# EIT_Teensy_Amplifiers.net
KiCad netlist of a schematic drawn in Altium Designer
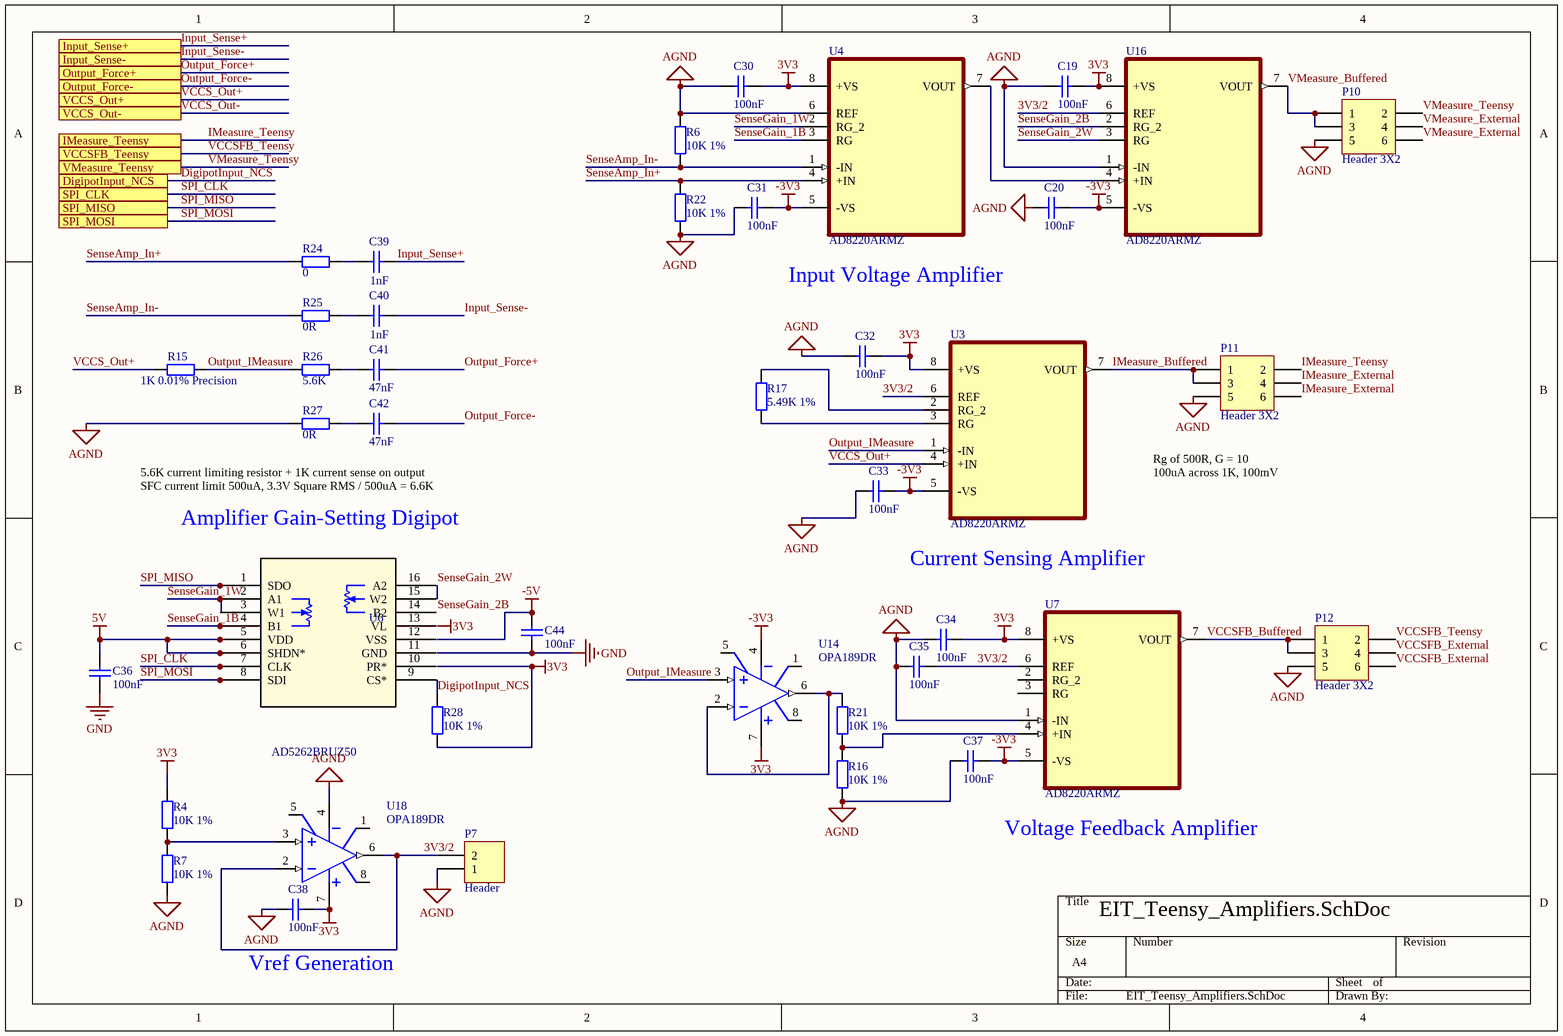
[diagram p0: EIT_Teensy_Amplifiers.SchDoc]

(export (version "E")
  (design (tool "Eeschema 10.0.6"))
  (components
    (comp (ref "C19")
      (value "100nF")
      (footprint "0603 CAP")
      (description "Multi Layer Ceramic Capacitor (MLCC) / Cap Ceramic 0.1uF 50V X7R 10% Pad SMD 0603 125°C T/R")
      (fields
        (field (name "MANUFACTURER") "Samsung")
        (field (name "MANUFACTURER PART NUMBER") "CL10B104KB8NNNC")
      )
      (libsource (lib "EitLib") (part "Cap 0603 100nF 10% 50V"))
    )
    (comp (ref "C20")
      (value "100nF")
      (footprint "0603 CAP")
      (description "Multi Layer Ceramic Capacitor (MLCC) / Cap Ceramic 0.1uF 50V X7R 10% Pad SMD 0603 125°C T/R")
      (fields
        (field (name "MANUFACTURER") "Samsung")
        (field (name "MANUFACTURER PART NUMBER") "CL10B104KB8NNNC")
      )
      (libsource (lib "EitLib") (part "Cap 0603 100nF 10% 50V"))
    )
    (comp (ref "C30")
      (value "100nF")
      (footprint "0603 CAP")
      (description "Multi Layer Ceramic Capacitor (MLCC) / Cap Ceramic 0.1uF 50V X7R 10% Pad SMD 0603 125°C T/R")
      (fields
        (field (name "MANUFACTURER") "Samsung")
        (field (name "MANUFACTURER PART NUMBER") "CL10B104KB8NNNC")
      )
      (libsource (lib "EitLib") (part "Cap 0603 100nF 10% 50V"))
    )
    (comp (ref "C31")
      (value "100nF")
      (footprint "0603 CAP")
      (description "Multi Layer Ceramic Capacitor (MLCC) / Cap Ceramic 0.1uF 50V X7R 10% Pad SMD 0603 125°C T/R")
      (fields
        (field (name "MANUFACTURER") "Samsung")
        (field (name "MANUFACTURER PART NUMBER") "CL10B104KB8NNNC")
      )
      (libsource (lib "EitLib") (part "Cap 0603 100nF 10% 50V"))
    )
    (comp (ref "C32")
      (value "100nF")
      (footprint "0603 CAP")
      (description "Multi Layer Ceramic Capacitor (MLCC) / Cap Ceramic 0.1uF 50V X7R 10% Pad SMD 0603 125°C T/R")
      (fields
        (field (name "MANUFACTURER") "Samsung")
        (field (name "MANUFACTURER PART NUMBER") "CL10B104KB8NNNC")
      )
      (libsource (lib "EitLib") (part "Cap 0603 100nF 10% 50V"))
    )
    (comp (ref "C33")
      (value "100nF")
      (footprint "0603 CAP")
      (description "Multi Layer Ceramic Capacitor (MLCC) / Cap Ceramic 0.1uF 50V X7R 10% Pad SMD 0603 125°C T/R")
      (fields
        (field (name "MANUFACTURER") "Samsung")
        (field (name "MANUFACTURER PART NUMBER") "CL10B104KB8NNNC")
      )
      (libsource (lib "EitLib") (part "Cap 0603 100nF 10% 50V"))
    )
    (comp (ref "C34")
      (value "100nF")
      (footprint "0603 CAP")
      (description "Multi Layer Ceramic Capacitor (MLCC) / Cap Ceramic 0.1uF 50V X7R 10% Pad SMD 0603 125°C T/R")
      (fields
        (field (name "MANUFACTURER") "Samsung")
        (field (name "MANUFACTURER PART NUMBER") "CL10B104KB8NNNC")
      )
      (libsource (lib "EitLib") (part "Cap 0603 100nF 10% 50V"))
    )
    (comp (ref "C35")
      (value "100nF")
      (footprint "0603 CAP")
      (description "Multi Layer Ceramic Capacitor (MLCC) / Cap Ceramic 0.1uF 50V X7R 10% Pad SMD 0603 125°C T/R")
      (fields
        (field (name "MANUFACTURER") "Samsung")
        (field (name "MANUFACTURER PART NUMBER") "CL10B104KB8NNNC")
      )
      (libsource (lib "EitLib") (part "Cap 0603 100nF 10% 50V"))
    )
    (comp (ref "C36")
      (value "100nF")
      (footprint "0603 CAP")
      (description "Multi Layer Ceramic Capacitor (MLCC) / Cap Ceramic 0.1uF 50V X7R 10% Pad SMD 0603 125°C T/R")
      (fields
        (field (name "MANUFACTURER") "Samsung")
        (field (name "MANUFACTURER PART NUMBER") "CL10B104KB8NNNC")
      )
      (libsource (lib "EitLib") (part "Cap 0603 100nF 10% 50V"))
    )
    (comp (ref "C37")
      (value "100nF")
      (footprint "0603 CAP")
      (description "Multi Layer Ceramic Capacitor (MLCC) / Cap Ceramic 0.1uF 50V X7R 10% Pad SMD 0603 125°C T/R")
      (fields
        (field (name "MANUFACTURER") "Samsung")
        (field (name "MANUFACTURER PART NUMBER") "CL10B104KB8NNNC")
      )
      (libsource (lib "EitLib") (part "Cap 0603 100nF 10% 50V"))
    )
    (comp (ref "C38")
      (value "100nF")
      (footprint "0603 CAP")
      (description "Multi Layer Ceramic Capacitor (MLCC) / Cap Ceramic 0.1uF 50V X7R 10% Pad SMD 0603 125°C T/R")
      (fields
        (field (name "MANUFACTURER") "Samsung")
        (field (name "MANUFACTURER PART NUMBER") "CL10B104KB8NNNC")
      )
      (libsource (lib "EitLib") (part "Cap 0603 100nF 10% 50V"))
    )
    (comp (ref "C39")
      (value "1nF")
      (footprint "RAD-0.3")
      (description "Capacitor")
      (fields (field (name "Comment") "Cap") (field (name "PUBLISHER") "Altium Limited"))
      (libsource (lib "Miscellaneous Devices") (part "Cap"))
    )
    (comp (ref "C40")
      (value "1nF")
      (footprint "RAD-0.3")
      (description "Capacitor")
      (fields (field (name "Comment") "Cap") (field (name "PUBLISHER") "Altium Limited"))
      (libsource (lib "Miscellaneous Devices") (part "Cap"))
    )
    (comp (ref "C41")
      (value "47nF")
      (footprint "0603 CAP")
      (description "CAP CER 0.047UF 50V X7R 0603")
      (fields
        (field (name "MANUFACTURER") "Samsung")
        (field (name "MANUFACTURER PART NUMBER") "CL10B473KB8NNNC")
      )
      (libsource (lib "EitLib") (part "Cap 0603 47nF 10% 50V"))
    )
    (comp (ref "C42")
      (value "47nF")
      (footprint "0603 CAP")
      (description "CAP CER 0.047UF 50V X7R 0603")
      (fields
        (field (name "MANUFACTURER") "Samsung")
        (field (name "MANUFACTURER PART NUMBER") "CL10B473KB8NNNC")
      )
      (libsource (lib "EitLib") (part "Cap 0603 47nF 10% 50V"))
    )
    (comp (ref "C44")
      (value "100nF")
      (footprint "0603 CAP")
      (description "Multi Layer Ceramic Capacitor (MLCC) / Cap Ceramic 0.1uF 50V X7R 10% Pad SMD 0603 125°C T/R")
      (fields
        (field (name "MANUFACTURER") "Samsung")
        (field (name "MANUFACTURER PART NUMBER") "CL10B104KB8NNNC")
      )
      (libsource (lib "EitLib") (part "Cap 0603 100nF 10% 50V"))
    )
    (comp (ref "P7")
      (value "Header")
      (footprint "HEADER 2.54MM 2X1 MALE")
      (description "CONN HEADER VERT 2POS 2.54MM")
      (fields
        (field (name "MANUFACTURER") "Sullins")
        (field (name "MANUFACTURER PART NUMBER") "PRPC002SAAN-RC")
      )
      (libsource (lib "EitLib") (part "Header 2x1 2.54mm T/H Male"))
    )
    (comp (ref "P10")
      (value "Header 3X2")
      (footprint "HDR2X3 Male 2.54mm")
      (description "Header, 3-Pin, Dual row")
      (libsource (lib "EitLib") (part "Header 3X2 2.54mm Male"))
    )
    (comp (ref "P11")
      (value "Header 3X2")
      (footprint "HDR2X3 Male 2.54mm")
      (description "Header, 3-Pin, Dual row")
      (libsource (lib "EitLib") (part "Header 3X2 2.54mm Male"))
    )
    (comp (ref "P12")
      (value "Header 3X2")
      (footprint "HDR2X3 Male 2.54mm")
      (description "Header, 3-Pin, Dual row")
      (libsource (lib "EitLib") (part "Header 3X2 2.54mm Male"))
    )
    (comp (ref "R4")
      (value "10K 1%")
      (footprint "0603 RES")
      (description "Res General Purpose Thick Film 0603 10K Ohm 1% 1/10W ±100ppm/°C Molded SMD Paper T/R")
      (fields
        (field (name "MANUFACTURER") "Yageo")
        (field (name "MANUFACTURER PART NUMBER") "RC0603FR-0710KL")
      )
      (libsource (lib "EitLib") (part "Res 0603 10K 1%"))
    )
    (comp (ref "R6")
      (value "10K 1%")
      (footprint "0603 RES")
      (description "Res General Purpose Thick Film 0603 10K Ohm 1% 1/10W ±100ppm/°C Molded SMD Paper T/R")
      (fields
        (field (name "MANUFACTURER") "Yageo")
        (field (name "MANUFACTURER PART NUMBER") "RC0603FR-0710KL")
      )
      (libsource (lib "") (part "Res 0603 10K 1%_1"))
    )
    (comp (ref "R7")
      (value "10K 1%")
      (footprint "0603 RES")
      (description "Res General Purpose Thick Film 0603 10K Ohm 1% 1/10W ±100ppm/°C Molded SMD Paper T/R")
      (fields
        (field (name "MANUFACTURER") "Yageo")
        (field (name "MANUFACTURER PART NUMBER") "RC0603FR-0710KL")
      )
      (libsource (lib "EitLib") (part "Res 0603 10K 1%"))
    )
    (comp (ref "R15")
      (value "1K 0.01% Precision")
      (footprint "0603 RES")
      (description "RES 1K OHM 0.01% 1/10W 0603")
      (fields
        (field (name "MANUFACTURER") "Stackpole Electronics")
        (field (name "MANUFACTURER PART NUMBER") "RNCF0603TKY1K00")
      )
      (libsource (lib "EitLib") (part "Res 0603 1K 0.01%"))
    )
    (comp (ref "R16")
      (value "10K 1%")
      (footprint "0603 RES")
      (description "Res General Purpose Thick Film 0603 10K Ohm 1% 1/10W ±100ppm/°C Molded SMD Paper T/R")
      (fields
        (field (name "MANUFACTURER") "Yageo")
        (field (name "MANUFACTURER PART NUMBER") "RC0603FR-0710KL")
      )
      (libsource (lib "") (part "Res 0603 10K 1%_1"))
    )
    (comp (ref "R17")
      (value "5.49K 1%")
      (footprint "0603 RES")
      (fields
        (field (name "MANUFACTURER") "Yageo")
        (field (name "MANUFACTURER PART NUMBER") "RC0603FR-075K49L")
        (field (name "TOLERANCE") "1%")
      )
      (libsource (lib "EitLib") (part "Res 0603 5.49K 1%"))
    )
    (comp (ref "R21")
      (value "10K 1%")
      (footprint "0603 RES")
      (description "Res General Purpose Thick Film 0603 10K Ohm 1% 1/10W ±100ppm/°C Molded SMD Paper T/R")
      (fields
        (field (name "MANUFACTURER") "Yageo")
        (field (name "MANUFACTURER PART NUMBER") "RC0603FR-0710KL")
      )
      (libsource (lib "") (part "Res 0603 10K 1%_1"))
    )
    (comp (ref "R22")
      (value "10K 1%")
      (footprint "0603 RES")
      (description "Res General Purpose Thick Film 0603 10K Ohm 1% 1/10W ±100ppm/°C Molded SMD Paper T/R")
      (fields
        (field (name "MANUFACTURER") "Yageo")
        (field (name "MANUFACTURER PART NUMBER") "RC0603FR-0710KL")
      )
      (libsource (lib "") (part "Res 0603 10K 1%_1"))
    )
    (comp (ref "R24")
      (value "0")
      (footprint "0603 RES")
      (description "RES SMD 4.7K OHM 1% 1/10W 0603")
      (fields
        (field (name "MANUFACTURER") "Yageo")
        (field (name "MANUFACTURER PART NUMBER") "RC0603FR-074K7L")
      )
      (libsource (lib "EitLib") (part "Res 0603 4.7K 1%"))
    )
    (comp (ref "R25")
      (value "0R")
      (footprint "0603 RES")
      (description "Resistor")
      (libsource (lib "EitLib") (part "Res 0603 template"))
    )
    (comp (ref "R26")
      (value "5.6K")
      (footprint "0603 RES")
      (description "Resistor")
      (libsource (lib "EitLib") (part "Res 0603 template"))
    )
    (comp (ref "R27")
      (value "0R")
      (footprint "0603 RES")
      (description "Resistor")
      (libsource (lib "EitLib") (part "Res 0603 template"))
    )
    (comp (ref "R28")
      (value "10K 1%")
      (footprint "0603 RES")
      (description "Res General Purpose Thick Film 0603 10K Ohm 1% 1/10W ±100ppm/°C Molded SMD Paper T/R")
      (fields
        (field (name "MANUFACTURER") "Yageo")
        (field (name "MANUFACTURER PART NUMBER") "RC0603FR-0710KL")
      )
      (libsource (lib "EitLib") (part "Res 0603 10K 1%"))
    )
    (comp (ref "U3")
      (value "AD8220ARMZ")
      (footprint "SOP65P490X110-8N")
      (description "ANALOG DEVICES   AD8220BRMZ   Instrument Amplifier, 1, 125 V, 2 V/s, 800 kHz,  2.25V to  18V, MSOP")
      (fields
        (field (name "MANUFACTURER") "Analog Devices")
        (field (name "MANUFACTURER PART NUMBER") "AD8220BRMZ")
      )
      (libsource (lib "EitLib") (part "AD8220ARMZ"))
    )
    (comp (ref "U4")
      (value "AD8220ARMZ")
      (footprint "SOP65P490X110-8N")
      (description "ANALOG DEVICES   AD8220BRMZ   Instrument Amplifier, 1, 125 V, 2 V/s, 800 kHz,  2.25V to  18V, MSOP")
      (fields
        (field (name "MANUFACTURER") "Analog Devices")
        (field (name "MANUFACTURER PART NUMBER") "AD8220BRMZ")
      )
      (libsource (lib "EitLib") (part "AD8220ARMZ"))
    )
    (comp (ref "U6")
      (value "AD5262BRUZ50")
      (description "Digital Potentiometer, 2 Func, 50000ohm, 3-wire Serial Control Interface, 256 Positions, PDSO16")
      (fields (field (name "MANUFACTURER") "Analog Devices"))
      (libsource (lib "EitLib") (part "AD5262BRUZ50"))
    )
    (comp (ref "U7")
      (value "AD8220ARMZ")
      (footprint "SOP65P490X110-8N")
      (description "ANALOG DEVICES   AD8220BRMZ   Instrument Amplifier, 1, 125 V, 2 V/s, 800 kHz,  2.25V to  18V, MSOP")
      (fields
        (field (name "MANUFACTURER") "Analog Devices")
        (field (name "MANUFACTURER PART NUMBER") "AD8220BRMZ")
      )
      (libsource (lib "EitLib") (part "AD8220ARMZ"))
    )
    (comp (ref "U14")
      (value "OPA189DR")
      (footprint "8-SOIC")
      (description "36V ZERO DRIFT OP-AMP")
      (fields
        (field (name "MANUFACTURER") "Texas Instruments")
        (field (name "MANUFACTURER PART NUMBER") "OPA189IDR")
      )
      (libsource (lib "EitLib") (part "OpAmp OPA189DR"))
    )
    (comp (ref "U16")
      (value "AD8220ARMZ")
      (footprint "SOP65P490X110-8N")
      (description "ANALOG DEVICES   AD8220BRMZ   Instrument Amplifier, 1, 125 V, 2 V/s, 800 kHz,  2.25V to  18V, MSOP")
      (fields
        (field (name "MANUFACTURER") "Analog Devices")
        (field (name "MANUFACTURER PART NUMBER") "AD8220BRMZ")
      )
      (libsource (lib "EitLib") (part "AD8220ARMZ"))
    )
    (comp (ref "U18")
      (value "OPA189DR")
      (footprint "8-SOIC")
      (description "36V ZERO DRIFT OP-AMP")
      (fields
        (field (name "MANUFACTURER") "Texas Instruments")
        (field (name "MANUFACTURER PART NUMBER") "OPA189IDR")
      )
      (libsource (lib "EitLib") (part "OpAmp OPA189DR"))
    )
  )
  (nets
    (net (code "1") (name "-3V3") (class "Default")
      (node (ref "C20") (pin "2") (pinfunction "2_2") (pintype "passive"))
      (node (ref "C31") (pin "2") (pinfunction "2_2") (pintype "passive"))
      (node (ref "C33") (pin "2") (pinfunction "2_2") (pintype "passive"))
      (node (ref "C37") (pin "2") (pinfunction "2_2") (pintype "passive"))
      (node (ref "U14") (pin "4") (pinfunction "V-_4") (pintype "power_in"))
      (node (ref "U16") (pin "5") (pinfunction "-VS_5") (pintype "power_in"))
      (node (ref "U3") (pin "5") (pinfunction "-VS_5") (pintype "power_in"))
      (node (ref "U4") (pin "5") (pinfunction "-VS_5") (pintype "power_in"))
      (node (ref "U7") (pin "5") (pinfunction "-VS_5") (pintype "power_in"))
    )
    (net (code "2") (name "-5V") (class "Default")
      (node (ref "C44") (pin "2") (pinfunction "2_2") (pintype "passive"))
    )
    (net (code "3") (name "/3V3{slash}2") (class "Default")
      (node (ref "C35") (pin "2") (pinfunction "2_2") (pintype "passive"))
      (node (ref "P7") (pin "2") (pinfunction "2_2") (pintype "passive"))
      (node (ref "U16") (pin "6") (pinfunction "REF_6") (pintype "passive"))
      (node (ref "U18") (pin "2") (pinfunction "IN-_2") (pintype "input"))
      (node (ref "U18") (pin "6") (pinfunction "OUT_6") (pintype "output"))
      (node (ref "U3") (pin "6") (pinfunction "REF_6") (pintype "passive"))
      (node (ref "U7") (pin "6") (pinfunction "REF_6") (pintype "passive"))
    )
    (net (code "4") (name "/DigipotInput_NCS") (class "Default")
      (node (ref "R28") (pin "2") (pinfunction "2_2") (pintype "passive"))
    )
    (net (code "5") (name "/IMeasure_Buffered") (class "Default")
      (node (ref "P11") (pin "1") (pinfunction "1_1") (pintype "passive"))
      (node (ref "P11") (pin "3") (pinfunction "3_3") (pintype "passive"))
      (node (ref "U3") (pin "7") (pinfunction "VOUT_7") (pintype "output"))
    )
    (net (code "6") (name "/IMeasure_External") (class "Default")
      (node (ref "P11") (pin "4") (pinfunction "4_4") (pintype "passive"))
      (node (ref "P11") (pin "6") (pinfunction "6_6") (pintype "passive"))
    )
    (net (code "7") (name "/IMeasure_Teensy") (class "Default")
      (node (ref "P11") (pin "2") (pinfunction "2_2") (pintype "passive"))
    )
    (net (code "8") (name "/Input_Sense+") (class "Default")
      (node (ref "C39") (pin "2") (pinfunction "2_2") (pintype "passive"))
    )
    (net (code "9") (name "/Input_Sense-") (class "Default")
      (node (ref "C40") (pin "2") (pinfunction "2_2") (pintype "passive"))
    )
    (net (code "10") (name "/Output_Force+") (class "Default")
      (node (ref "C41") (pin "2") (pinfunction "2_2") (pintype "passive"))
    )
    (net (code "11") (name "/Output_Force-") (class "Default")
      (node (ref "C42") (pin "2") (pinfunction "2_2") (pintype "passive"))
    )
    (net (code "12") (name "/Output_IMeasure") (class "Default")
      (node (ref "R15") (pin "2") (pinfunction "2_2") (pintype "passive"))
      (node (ref "R26") (pin "1") (pinfunction "1_1") (pintype "passive"))
      (node (ref "U14") (pin "3") (pinfunction "IN+_3") (pintype "input"))
      (node (ref "U3") (pin "1") (pinfunction "-IN_1") (pintype "input"))
    )
    (net (code "13") (name "/SPI_CLK") (class "Default")
      (node (ref "U6") (pin "7") (pinfunction "CLK_7") (pintype "passive"))
    )
    (net (code "14") (name "/SPI_MISO") (class "Default")
      (node (ref "U6") (pin "1") (pinfunction "SDO_1") (pintype "passive"))
    )
    (net (code "15") (name "/SPI_MOSI") (class "Default")
      (node (ref "U6") (pin "8") (pinfunction "SDI_8") (pintype "passive"))
    )
    (net (code "16") (name "/SenseAmp_In+") (class "Default")
      (node (ref "R22") (pin "1") (pinfunction "1_1") (pintype "passive"))
      (node (ref "R24") (pin "1") (pinfunction "1_1") (pintype "passive"))
      (node (ref "U4") (pin "4") (pinfunction "+IN_4") (pintype "input"))
    )
    (net (code "17") (name "/SenseAmp_In-") (class "Default")
      (node (ref "R25") (pin "1") (pinfunction "1_1") (pintype "passive"))
      (node (ref "R6") (pin "2") (pinfunction "2_2") (pintype "passive"))
      (node (ref "U4") (pin "1") (pinfunction "-IN_1") (pintype "input"))
    )
    (net (code "18") (name "/SenseGain_1B") (class "Default")
      (node (ref "U4") (pin "3") (pinfunction "RG_3") (pintype "passive"))
      (node (ref "U6") (pin "4") (pinfunction "B1_4") (pintype "passive"))
    )
    (net (code "19") (name "/SenseGain_1W") (class "Default")
      (node (ref "U4") (pin "2") (pinfunction "RG_2_2") (pintype "passive"))
      (node (ref "U6") (pin "2") (pinfunction "A1_2") (pintype "passive"))
    )
    (net (code "20") (name "/SenseGain_2B") (class "Default")
      (node (ref "U16") (pin "2") (pinfunction "RG_2_2") (pintype "passive"))
    )
    (net (code "21") (name "/SenseGain_2W") (class "Default")
      (node (ref "U16") (pin "3") (pinfunction "RG_3") (pintype "passive"))
    )
    (net (code "22") (name "/VCCSFB_Buffered") (class "Default")
      (node (ref "P12") (pin "1") (pinfunction "1_1") (pintype "passive"))
      (node (ref "P12") (pin "3") (pinfunction "3_3") (pintype "passive"))
      (node (ref "U7") (pin "7") (pinfunction "VOUT_7") (pintype "output"))
    )
    (net (code "23") (name "/VCCSFB_External") (class "Default")
      (node (ref "P12") (pin "4") (pinfunction "4_4") (pintype "passive"))
      (node (ref "P12") (pin "6") (pinfunction "6_6") (pintype "passive"))
    )
    (net (code "24") (name "/VCCSFB_Teensy") (class "Default")
      (node (ref "P12") (pin "2") (pinfunction "2_2") (pintype "passive"))
    )
    (net (code "25") (name "/VCCS_Out+") (class "Default")
      (node (ref "R15") (pin "1") (pinfunction "1_1") (pintype "passive"))
      (node (ref "U3") (pin "4") (pinfunction "+IN_4") (pintype "input"))
    )
    (net (code "27") (name "/VMeasure_Buffered") (class "Default")
      (node (ref "P10") (pin "1") (pinfunction "1_1") (pintype "passive"))
      (node (ref "P10") (pin "3") (pinfunction "3_3") (pintype "passive"))
      (node (ref "U16") (pin "7") (pinfunction "VOUT_7") (pintype "output"))
    )
    (net (code "28") (name "/VMeasure_External") (class "Default")
      (node (ref "P10") (pin "4") (pinfunction "4_4") (pintype "passive"))
      (node (ref "P10") (pin "6") (pinfunction "6_6") (pintype "passive"))
    )
    (net (code "29") (name "/VMeasure_Teensy") (class "Default")
      (node (ref "P10") (pin "2") (pinfunction "2_2") (pintype "passive"))
    )
    (net (code "30") (name "3V3") (class "Default")
      (node (ref "C19") (pin "2") (pinfunction "2_2") (pintype "passive"))
      (node (ref "C30") (pin "2") (pinfunction "2_2") (pintype "passive"))
      (node (ref "C32") (pin "2") (pinfunction "2_2") (pintype "passive"))
      (node (ref "C34") (pin "2") (pinfunction "2_2") (pintype "passive"))
      (node (ref "C38") (pin "2") (pinfunction "2_2") (pintype "passive"))
      (node (ref "R28") (pin "1") (pinfunction "1_1") (pintype "passive"))
      (node (ref "R4") (pin "2") (pinfunction "2_2") (pintype "passive"))
      (node (ref "U14") (pin "7") (pinfunction "V+_7") (pintype "power_in"))
      (node (ref "U16") (pin "8") (pinfunction "+VS_8") (pintype "power_in"))
      (node (ref "U18") (pin "7") (pinfunction "V+_7") (pintype "power_in"))
      (node (ref "U3") (pin "8") (pinfunction "+VS_8") (pintype "power_in"))
      (node (ref "U4") (pin "8") (pinfunction "+VS_8") (pintype "power_in"))
      (node (ref "U7") (pin "8") (pinfunction "+VS_8") (pintype "power_in"))
    )
    (net (code "31") (name "5V") (class "Default")
      (node (ref "C36") (pin "2") (pinfunction "2_2") (pintype "passive"))
      (node (ref "U6") (pin "5") (pinfunction "VDD_5") (pintype "power_in"))
      (node (ref "U6") (pin "6") (pinfunction "SHDN*_6") (pintype "passive"))
    )
    (net (code "32") (name "AGND") (class "Default")
      (node (ref "C19") (pin "1") (pinfunction "1_1") (pintype "passive"))
      (node (ref "C20") (pin "1") (pinfunction "1_1") (pintype "passive"))
      (node (ref "C30") (pin "1") (pinfunction "1_1") (pintype "passive"))
      (node (ref "C31") (pin "1") (pinfunction "1_1") (pintype "passive"))
      (node (ref "C32") (pin "1") (pinfunction "1_1") (pintype "passive"))
      (node (ref "C33") (pin "1") (pinfunction "1_1") (pintype "passive"))
      (node (ref "C34") (pin "1") (pinfunction "1_1") (pintype "passive"))
      (node (ref "C35") (pin "1") (pinfunction "1_1") (pintype "passive"))
      (node (ref "C37") (pin "1") (pinfunction "1_1") (pintype "passive"))
      (node (ref "C38") (pin "1") (pinfunction "1_1") (pintype "passive"))
      (node (ref "P10") (pin "5") (pinfunction "5_5") (pintype "passive"))
      (node (ref "P11") (pin "5") (pinfunction "5_5") (pintype "passive"))
      (node (ref "P12") (pin "5") (pinfunction "5_5") (pintype "passive"))
      (node (ref "P7") (pin "1") (pinfunction "1_1") (pintype "passive"))
      (node (ref "R16") (pin "2") (pinfunction "2_2") (pintype "passive"))
      (node (ref "R22") (pin "2") (pinfunction "2_2") (pintype "passive"))
      (node (ref "R27") (pin "1") (pinfunction "1_1") (pintype "passive"))
      (node (ref "R6") (pin "1") (pinfunction "1_1") (pintype "passive"))
      (node (ref "R7") (pin "1") (pinfunction "1_1") (pintype "passive"))
      (node (ref "U16") (pin "1") (pinfunction "-IN_1") (pintype "input"))
      (node (ref "U18") (pin "4") (pinfunction "V-_4") (pintype "power_in"))
      (node (ref "U4") (pin "6") (pinfunction "REF_6") (pintype "passive"))
      (node (ref "U7") (pin "1") (pinfunction "-IN_1") (pintype "input"))
    )
    (net (code "33") (name "GND") (class "Default")
      (node (ref "C36") (pin "1") (pinfunction "1_1") (pintype "passive"))
      (node (ref "C44") (pin "1") (pinfunction "1_1") (pintype "passive"))
    )
    (net (code "34") (name "Net-(C39-Pad1)") (class "Default")
      (node (ref "C39") (pin "1") (pinfunction "1_1") (pintype "passive"))
      (node (ref "R24") (pin "2") (pinfunction "2_2") (pintype "passive"))
    )
    (net (code "35") (name "Net-(C40-Pad1)") (class "Default")
      (node (ref "C40") (pin "1") (pinfunction "1_1") (pintype "passive"))
      (node (ref "R25") (pin "2") (pinfunction "2_2") (pintype "passive"))
    )
    (net (code "36") (name "Net-(C41-Pad1)") (class "Default")
      (node (ref "C41") (pin "1") (pinfunction "1_1") (pintype "passive"))
      (node (ref "R26") (pin "2") (pinfunction "2_2") (pintype "passive"))
    )
    (net (code "37") (name "Net-(C42-Pad1)") (class "Default")
      (node (ref "C42") (pin "1") (pinfunction "1_1") (pintype "passive"))
      (node (ref "R27") (pin "2") (pinfunction "2_2") (pintype "passive"))
    )
    (net (code "38") (name "Net-(U3-RG)") (class "Default")
      (node (ref "R17") (pin "2") (pinfunction "2_2") (pintype "passive"))
      (node (ref "U3") (pin "3") (pinfunction "RG_3") (pintype "passive"))
    )
    (net (code "39") (name "Net-(U3-RG_2)") (class "Default")
      (node (ref "R17") (pin "1") (pinfunction "1_1") (pintype "passive"))
      (node (ref "U3") (pin "2") (pinfunction "RG_2_2") (pintype "passive"))
    )
    (net (code "40") (name "Net-(U7-+IN)") (class "Default")
      (node (ref "R16") (pin "1") (pinfunction "1_1") (pintype "passive"))
      (node (ref "R21") (pin "2") (pinfunction "2_2") (pintype "passive"))
      (node (ref "U7") (pin "4") (pinfunction "+IN_4") (pintype "input"))
    )
    (net (code "41") (name "Net-(U14-IN-)") (class "Default")
      (node (ref "R21") (pin "1") (pinfunction "1_1") (pintype "passive"))
      (node (ref "U14") (pin "2") (pinfunction "IN-_2") (pintype "input"))
      (node (ref "U14") (pin "6") (pinfunction "OUT_6") (pintype "output"))
    )
    (net (code "42") (name "Net-(U16-+IN)") (class "Default")
      (node (ref "U16") (pin "4") (pinfunction "+IN_4") (pintype "input"))
      (node (ref "U4") (pin "7") (pinfunction "VOUT_7") (pintype "output"))
    )
    (net (code "43") (name "Net-(U18-IN+)") (class "Default")
      (node (ref "R4") (pin "1") (pinfunction "1_1") (pintype "passive"))
      (node (ref "R7") (pin "2") (pinfunction "2_2") (pintype "passive"))
      (node (ref "U18") (pin "3") (pinfunction "IN+_3") (pintype "input"))
    )
    (net (code "44") (name "unconnected-(U6-A2-Pad16)") (class "Default")
      (node (ref "U6") (pin "16") (pinfunction "A2_16") (pintype "passive"))
    )
    (net (code "45") (name "unconnected-(U6-B2-Pad14)") (class "Default")
      (node (ref "U6") (pin "14") (pinfunction "B2_14") (pintype "passive"))
    )
    (net (code "46") (name "unconnected-(U6-CS*-Pad9)") (class "Default")
      (node (ref "U6") (pin "9") (pinfunction "CS*_9") (pintype "passive"))
    )
    (net (code "47") (name "unconnected-(U6-GND-Pad11)") (class "Default")
      (node (ref "U6") (pin "11") (pinfunction "GND_11") (pintype "passive"))
    )
    (net (code "48") (name "unconnected-(U6-PR*-Pad10)") (class "Default")
      (node (ref "U6") (pin "10") (pinfunction "PR*_10") (pintype "passive"))
    )
    (net (code "49") (name "unconnected-(U6-VL-Pad13)") (class "Default")
      (node (ref "U6") (pin "13") (pinfunction "VL_13") (pintype "power_in"))
    )
    (net (code "50") (name "unconnected-(U6-VSS-Pad12)") (class "Default")
      (node (ref "U6") (pin "12") (pinfunction "VSS_12") (pintype "power_in"))
    )
    (net (code "51") (name "unconnected-(U6-W1-Pad3)") (class "Default")
      (node (ref "U6") (pin "3") (pinfunction "W1_3") (pintype "passive"))
    )
    (net (code "52") (name "unconnected-(U6-W2-Pad15)") (class "Default")
      (node (ref "U6") (pin "15") (pinfunction "W2_15") (pintype "passive"))
    )
    (net (code "53") (name "unconnected-(U7-RG-Pad3)") (class "Default")
      (node (ref "U7") (pin "3") (pinfunction "RG_3") (pintype "passive"))
    )
    (net (code "54") (name "unconnected-(U7-RG_2-Pad2)") (class "Default")
      (node (ref "U7") (pin "2") (pinfunction "RG_2_2") (pintype "passive"))
    )
    (net (code "55") (name "unconnected-(U14-OS_NUL-Pad1)") (class "Default")
      (node (ref "U14") (pin "1") (pinfunction "OS_NUL_1") (pintype "passive"))
    )
    (net (code "56") (name "unconnected-(U14-OS_NUL-Pad5)") (class "Default")
      (node (ref "U14") (pin "5") (pinfunction "OS_NUL_5") (pintype "passive"))
    )
    (net (code "57") (name "unconnected-(U14-TAB-Pad8)") (class "Default")
      (node (ref "U14") (pin "8") (pinfunction "TAB_8") (pintype "passive"))
    )
    (net (code "58") (name "unconnected-(U18-OS_NUL-Pad1)") (class "Default")
      (node (ref "U18") (pin "1") (pinfunction "OS_NUL_1") (pintype "passive"))
    )
    (net (code "59") (name "unconnected-(U18-OS_NUL-Pad5)") (class "Default")
      (node (ref "U18") (pin "5") (pinfunction "OS_NUL_5") (pintype "passive"))
    )
    (net (code "60") (name "unconnected-(U18-TAB-Pad8)") (class "Default")
      (node (ref "U18") (pin "8") (pinfunction "TAB_8") (pintype "passive"))
    )
  )
)
